# AT24Cxxx_EEPROM_I2C.net
KiCad netlist of a schematic drawn in Altium Designer
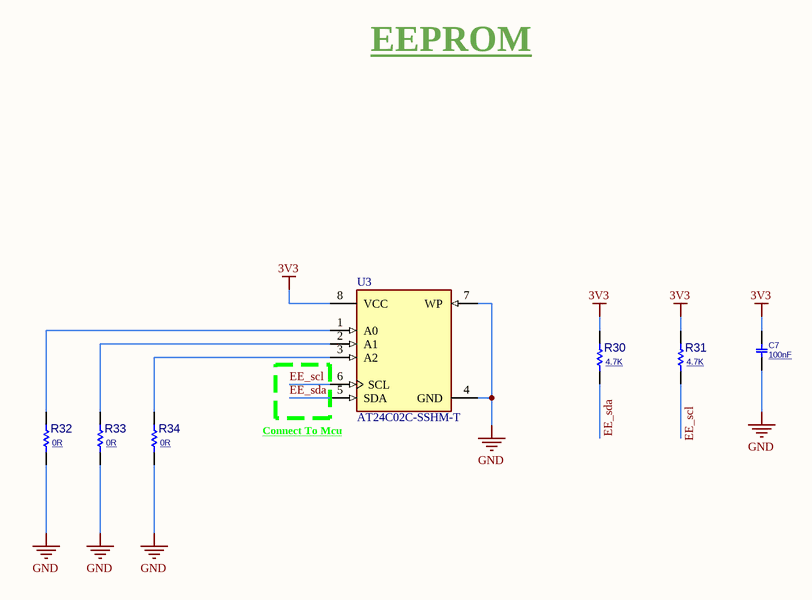
[diagram p0: AT24Cxxx_EEPROM_I2C.SchDoc]

(export (version "E")
  (design (tool "Eeschema 10.0.6"))
  (components
    (comp (ref "C7")
      (value "100nF")
      (footprint "C0603")
      (description "CAP, MLCC, -F, -V, MATERIAL, -%, 0201")
      (fields (field (name "MANF_P#") "MANF_PART#"))
      (libsource (lib "passive_smd") (part "CAP_SMD_MLCC_0603"))
    )
    (comp (ref "R30")
      (value "4.7K")
      (footprint "R0603")
      (description "RESISTOR, SMD")
      (libsource (lib "passive_smd") (part "RES_SMD"))
    )
    (comp (ref "R31")
      (value "4.7K")
      (footprint "R0603")
      (description "RESISTOR, SMD")
      (libsource (lib "passive_smd") (part "RES_SMD"))
    )
    (comp (ref "R32")
      (value "0R")
      (footprint "R0603")
      (description "RESISTOR, SMD")
      (libsource (lib "passive_smd") (part "RES_SMD"))
    )
    (comp (ref "R33")
      (value "0R")
      (footprint "R0603")
      (description "RESISTOR, SMD")
      (libsource (lib "passive_smd") (part "RES_SMD"))
    )
    (comp (ref "R34")
      (value "0R")
      (footprint "R0603")
      (description "RESISTOR, SMD")
      (libsource (lib "passive_smd") (part "RES_SMD"))
    )
    (comp (ref "U3")
      (value "AT24C02C-SSHM-T")
      (footprint "FP-C04-057-SN-MFG")
      (description "IC EEPROM 2K I2C 1MHZ 8SOIC")
      (fields
        (field (name "OCTOPART") "https://octopart.com/at24c02c-sshm-t-microchip-77757935")
        (field (name "MANUFACTURER") "Microchip")
      )
      (libsource (lib "Altium Content Vault") (part "10b14863ecfc9a00679244ba73e2fea"))
    )
  )
  (nets
    (net (code "1") (name "/EE_scl") (class "Default")
      (node (ref "R31") (pin "1") (pinfunction "1_1") (pintype "passive"))
      (node (ref "U3") (pin "6") (pinfunction "SCL_6") (pintype "input"))
    )
    (net (code "2") (name "/EE_sda") (class "Default")
      (node (ref "R30") (pin "1") (pinfunction "1_1") (pintype "passive"))
      (node (ref "U3") (pin "5") (pinfunction "SDA_5") (pintype "input"))
    )
    (net (code "3") (name "3V3") (class "Default")
      (node (ref "C7") (pin "2") (pinfunction "2_2") (pintype "passive"))
      (node (ref "R30") (pin "2") (pinfunction "2_2") (pintype "passive"))
      (node (ref "R31") (pin "2") (pinfunction "2_2") (pintype "passive"))
      (node (ref "U3") (pin "8") (pinfunction "VCC_8") (pintype "power_in"))
    )
    (net (code "4") (name "GND") (class "Default")
      (node (ref "C7") (pin "1") (pinfunction "1_1") (pintype "passive"))
      (node (ref "R32") (pin "1") (pinfunction "1_1") (pintype "passive"))
      (node (ref "R33") (pin "1") (pinfunction "1_1") (pintype "passive"))
      (node (ref "R34") (pin "1") (pinfunction "1_1") (pintype "passive"))
      (node (ref "U3") (pin "4") (pinfunction "GND_4") (pintype "power_in"))
      (node (ref "U3") (pin "7") (pinfunction "WP_7") (pintype "input"))
    )
    (net (code "5") (name "Net-(U3-A0)") (class "Default")
      (node (ref "R32") (pin "2") (pinfunction "2_2") (pintype "passive"))
      (node (ref "U3") (pin "1") (pinfunction "A0_1") (pintype "input"))
    )
    (net (code "6") (name "Net-(U3-A1)") (class "Default")
      (node (ref "R33") (pin "2") (pinfunction "2_2") (pintype "passive"))
      (node (ref "U3") (pin "2") (pinfunction "A1_2") (pintype "input"))
    )
    (net (code "7") (name "Net-(U3-A2)") (class "Default")
      (node (ref "R34") (pin "2") (pinfunction "2_2") (pintype "passive"))
      (node (ref "U3") (pin "3") (pinfunction "A2_3") (pintype "input"))
    )
  )
)
